# Sheet1.net
KiCad netlist of a schematic drawn in Altium Designer
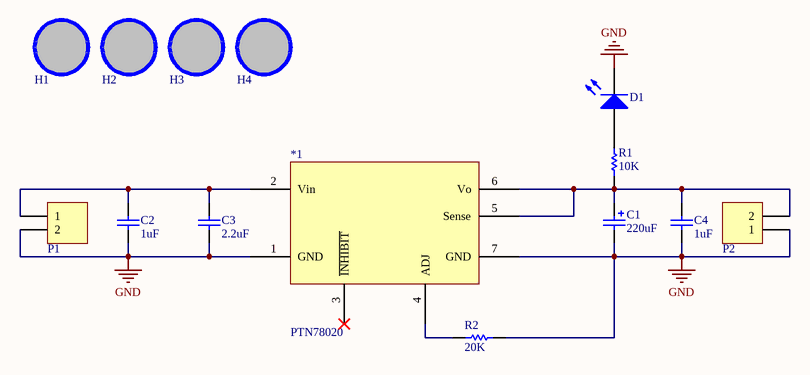
[diagram p0: Sheet1.SchDoc]

(export (version "E")
  (design (tool "Eeschema 10.0.6"))
  (components
    (comp (ref "*1")
      (value "PTN78020")
      (footprint "PTN78020H")
      (libsource (lib "MiclsLib") (part "PTN78020"))
    )
    (comp (ref "C1")
      (value "220uF")
      (footprint "CAP ALU SIZE D")
      (description "Polarized Capacitor (Radial)")
      (fields (field (name "Comment") "Cap Pol SMD"))
      (libsource (lib "PIF_Library") (part "Cap Pol SMD"))
    )
    (comp (ref "C2")
      (value "1uF")
      (footprint "CAP-SM-0603")
      (description "Capacitor")
      (fields (field (name "Comment") "Cap Non-Pol SMD"))
      (libsource (lib "PIF_Library") (part "Cap Non-Pol SMD"))
    )
    (comp (ref "C3")
      (value "2.2uF")
      (footprint "CAP-SM-0603")
      (description "Capacitor")
      (fields (field (name "Comment") "Cap Non-Pol SMD"))
      (libsource (lib "PIF_Library") (part "Cap Non-Pol SMD"))
    )
    (comp (ref "C4")
      (value "1uF")
      (footprint "CAP-SM-0603")
      (description "Capacitor")
      (fields (field (name "Comment") "Cap Non-Pol SMD"))
      (libsource (lib "PIF_Library") (part "Cap Non-Pol SMD"))
    )
    (comp (ref "D1")
      (value "LED SMD")
      (footprint "LED_0603_Blue")
      (description "LED")
      (libsource (lib "PIF_Library") (part "LED SMD"))
    )
    (comp (ref "H1")
      (value "Hole")
      (footprint "LO KHOAN 3MM")
      (description "Hole 3mm")
      (libsource (lib "PIF_Library") (part "Hole"))
    )
    (comp (ref "H2")
      (value "Hole")
      (footprint "LO KHOAN 3MM")
      (description "Hole 3mm")
      (libsource (lib "PIF_Library") (part "Hole"))
    )
    (comp (ref "H3")
      (value "Hole")
      (footprint "LO KHOAN 3MM")
      (description "Hole 3mm")
      (libsource (lib "PIF_Library") (part "Hole"))
    )
    (comp (ref "H4")
      (value "Hole")
      (footprint "LO KHOAN 3MM")
      (description "Hole 3mm")
      (libsource (lib "PIF_Library") (part "Hole"))
    )
    (comp (ref "P1")
      (value "Domino 2")
      (footprint "DOMINO 2- 5mm")
      (description "Domino, 2-Pin")
      (fields (field (name "PUBLISHER") "Altium Limited"))
      (libsource (lib "") (part "Domino 2_1"))
    )
    (comp (ref "P2")
      (value "Domino 2")
      (footprint "DOMINO 2- 5mm")
      (description "Domino, 2-Pin")
      (fields (field (name "PUBLISHER") "Altium Limited"))
      (libsource (lib "PIF_Library") (part "Domino 2"))
    )
    (comp (ref "R1")
      (value "10K")
      (footprint "RES-SM-0603")
      (description "Resistor")
      (fields (field (name "Comment") "RESISTOR SMD"))
      (libsource (lib "PIF_Library") (part "RESISTOR SMD"))
    )
    (comp (ref "R2")
      (value "20K")
      (footprint "RES-SM-0603")
      (description "Resistor")
      (fields (field (name "Comment") "RESISTOR SMD"))
      (libsource (lib "PIF_Library") (part "RESISTOR SMD"))
    )
  )
  (nets
    (net (code "1") (name "GND") (class "Default")
      (node (ref "*1") (pin "1") (pinfunction "GND_1") (pintype "passive"))
      (node (ref "*1") (pin "7") (pinfunction "GND_7") (pintype "passive"))
      (node (ref "C1") (pin "2") (pinfunction "2_2") (pintype "passive"))
      (node (ref "C2") (pin "1") (pinfunction "1_1") (pintype "passive"))
      (node (ref "C3") (pin "1") (pinfunction "1_1") (pintype "passive"))
      (node (ref "C4") (pin "1") (pinfunction "1_1") (pintype "passive"))
      (node (ref "D1") (pin "2") (pinfunction "K_2") (pintype "passive"))
      (node (ref "P1") (pin "2") (pinfunction "2_2") (pintype "passive"))
      (node (ref "P2") (pin "1") (pinfunction "1_1") (pintype "passive"))
      (node (ref "R2") (pin "2") (pinfunction "2_2") (pintype "passive"))
    )
    (net (code "2") (name "Net-(*1-ADJ)") (class "Default")
      (node (ref "*1") (pin "4") (pinfunction "ADJ_4") (pintype "passive"))
      (node (ref "R2") (pin "1") (pinfunction "1_1") (pintype "passive"))
    )
    (net (code "3") (name "Net-(*1-Sense)") (class "Default")
      (node (ref "*1") (pin "5") (pinfunction "Sense_5") (pintype "passive"))
      (node (ref "*1") (pin "6") (pinfunction "Vo_6") (pintype "passive"))
      (node (ref "C1") (pin "1") (pinfunction "1_1") (pintype "passive"))
      (node (ref "C4") (pin "2") (pinfunction "2_2") (pintype "passive"))
      (node (ref "P2") (pin "2") (pinfunction "2_2") (pintype "passive"))
      (node (ref "R1") (pin "1") (pinfunction "1_1") (pintype "passive"))
    )
    (net (code "4") (name "Net-(*1-Vin)") (class "Default")
      (node (ref "*1") (pin "2") (pinfunction "Vin_2") (pintype "passive"))
      (node (ref "C2") (pin "2") (pinfunction "2_2") (pintype "passive"))
      (node (ref "C3") (pin "2") (pinfunction "2_2") (pintype "passive"))
      (node (ref "P1") (pin "1") (pinfunction "1_1") (pintype "passive"))
    )
    (net (code "5") (name "Net-(D1-A)") (class "Default")
      (node (ref "D1") (pin "1") (pinfunction "A_1") (pintype "passive"))
      (node (ref "R1") (pin "2") (pinfunction "2_2") (pintype "passive"))
    )
    (net (code "6") (name "unconnected-(*1-~{INHIBIT}-Pad3)") (class "Default")
      (node (ref "*1") (pin "3") (pinfunction "~{INHIBIT}_3") (pintype "passive+no_connect"))
    )
    (net (code "7") (name "unconnected-(H1-Pad1)") (class "Default")
      (node (ref "H1") (pin "1") (pinfunction "1_1") (pintype "passive"))
    )
    (net (code "8") (name "unconnected-(H2-Pad1)") (class "Default")
      (node (ref "H2") (pin "1") (pinfunction "1_1") (pintype "passive"))
    )
    (net (code "9") (name "unconnected-(H3-Pad1)") (class "Default")
      (node (ref "H3") (pin "1") (pinfunction "1_1") (pintype "passive"))
    )
    (net (code "10") (name "unconnected-(H4-Pad1)") (class "Default")
      (node (ref "H4") (pin "1") (pinfunction "1_1") (pintype "passive"))
    )
  )
)
